# SHT31_2.net
KiCad netlist of a schematic drawn in EAGLE
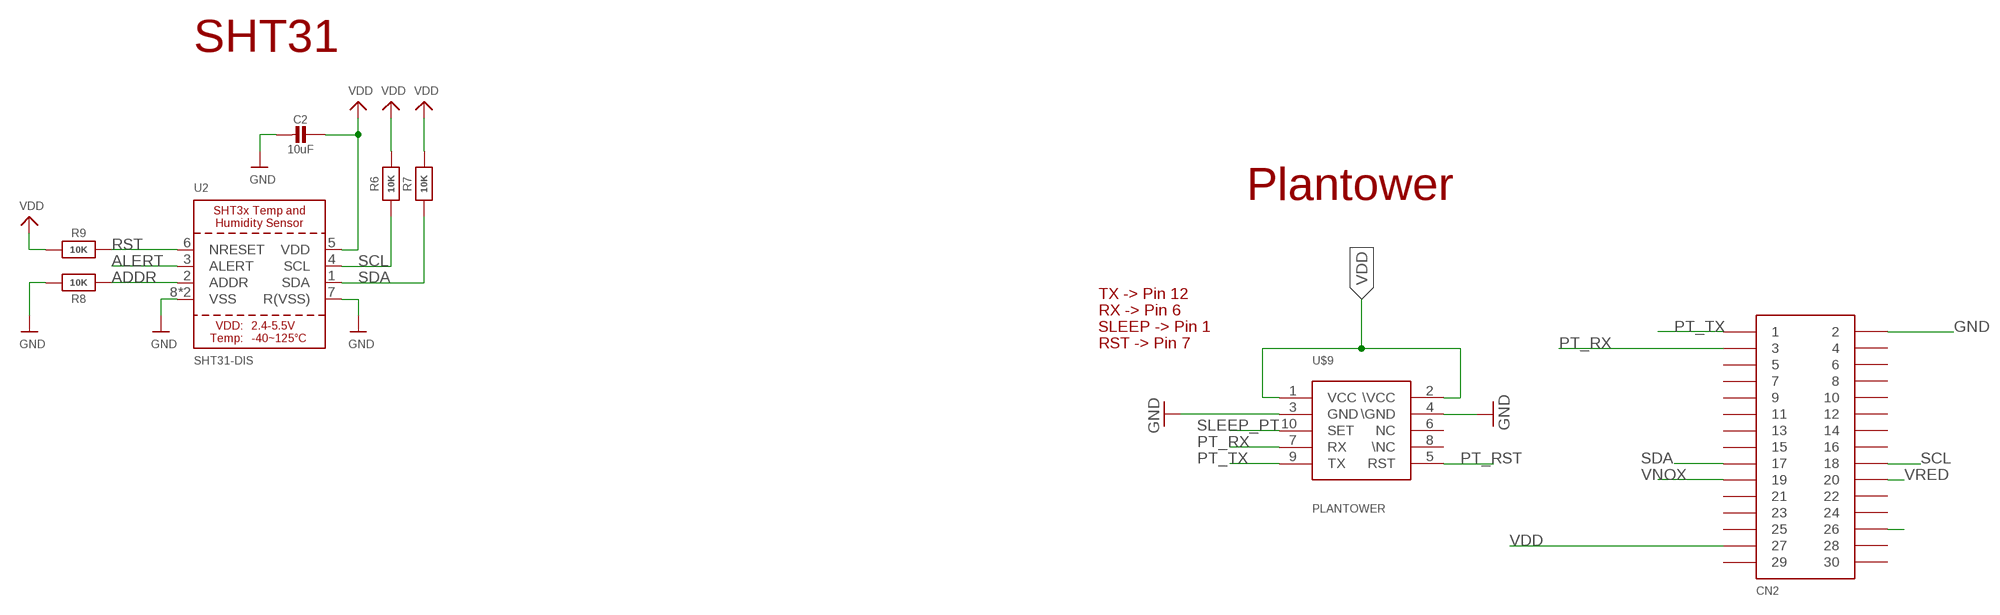
[diagram p0: schematic, sheet 1]
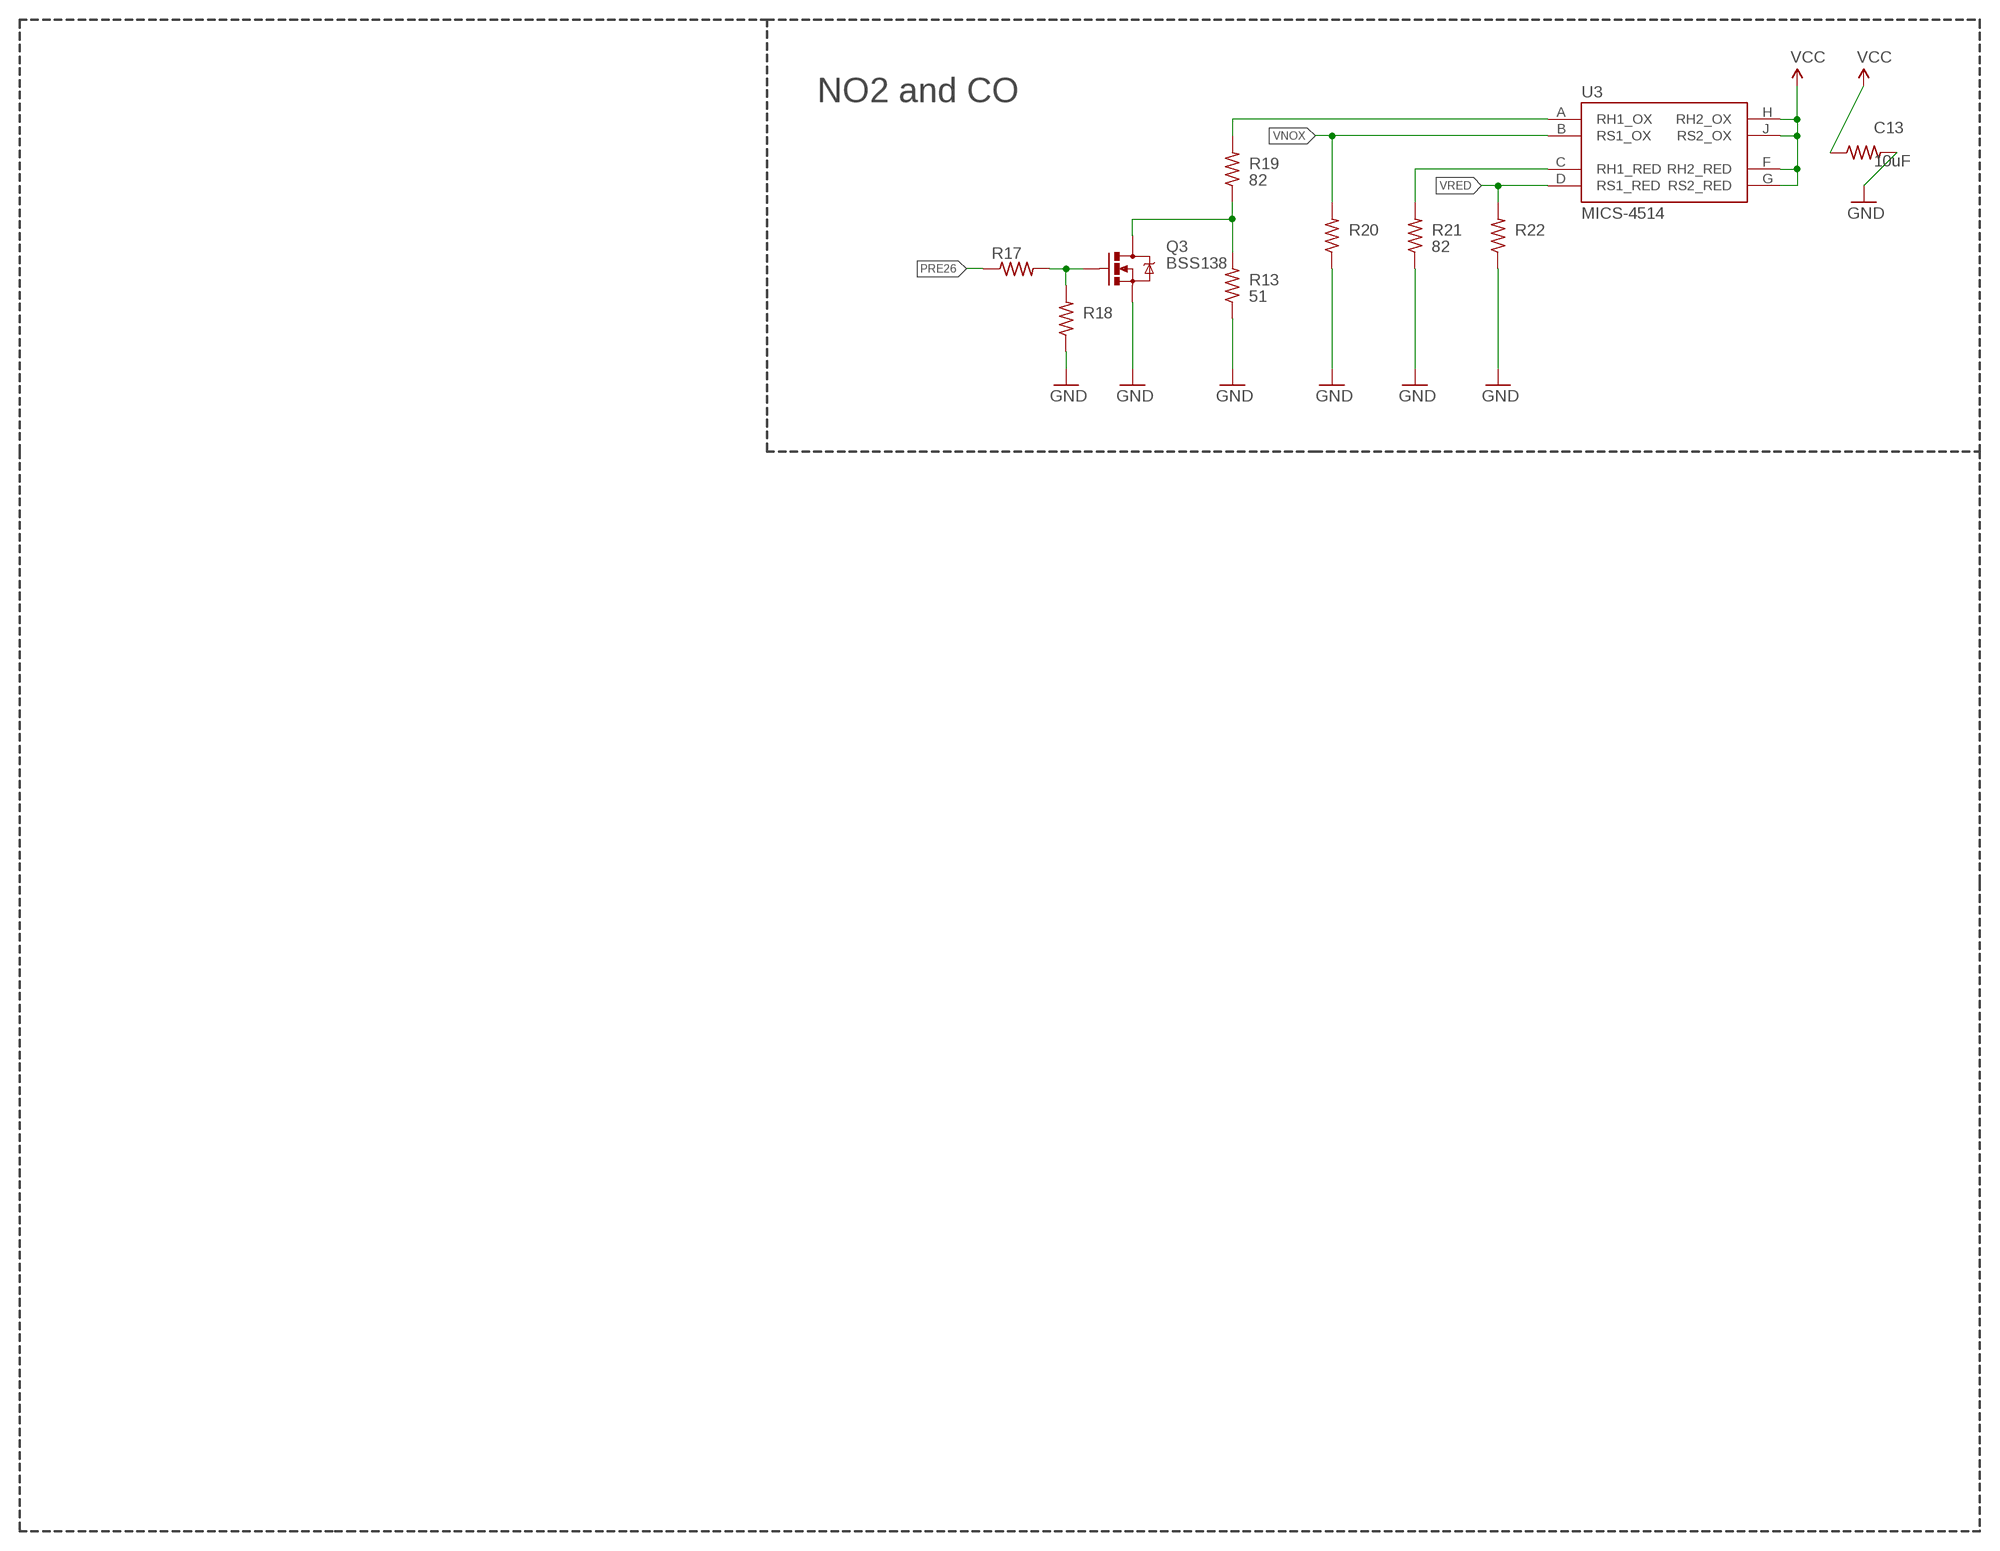
[diagram p1: schematic, sheet 2]

(export (version "E")
  (design (tool "Eeschema 10.0.6"))
  (components
    (comp (ref "C13")
      (value "10uF")
      (footprint "eagle-import:R1206FAB")
      (libsource (lib "eagle-import") (part "RES-US1206FAB"))
    )
    (comp (ref "Q3")
      (value "MOSFET-NCHANNELBSS138")
      (footprint "eagle-import:SOT23-3")
      (fields (field (name "P_NAME") "BSS138"))
      (libsource (lib "eagle-import") (part "MOSFET-NCHANNELBSS138"))
    )
    (comp (ref "R13")
      (value "51")
      (footprint "eagle-import:R1206FAB")
      (libsource (lib "eagle-import") (part "RES-US1206FAB"))
    )
    (comp (ref "R17")
      (value "100")
      (footprint "eagle-import:R1206FAB")
      (libsource (lib "eagle-import") (part "RES-US1206FAB"))
    )
    (comp (ref "R18")
      (value "100K")
      (footprint "eagle-import:R1206FAB")
      (libsource (lib "eagle-import") (part "RES-US1206FAB"))
    )
    (comp (ref "R19")
      (value "82")
      (footprint "eagle-import:R1206FAB")
      (libsource (lib "eagle-import") (part "RES-US1206FAB"))
    )
    (comp (ref "R20")
      (value "22K")
      (footprint "eagle-import:R1206FAB")
      (libsource (lib "eagle-import") (part "RES-US1206FAB"))
    )
    (comp (ref "R21")
      (value "82")
      (footprint "eagle-import:R1206FAB")
      (libsource (lib "eagle-import") (part "RES-US1206FAB"))
    )
    (comp (ref "R22")
      (value "47K")
      (footprint "eagle-import:R1206FAB")
      (libsource (lib "eagle-import") (part "RES-US1206FAB"))
    )
    (comp (ref "U3")
      (value "MICS-4514")
      (footprint "eagle-import:MICS_10-SMD")
      (libsource (lib "eagle-import") (part "MICS-4514"))
    )
    (comp (ref "C2")
      (value "10uF")
      (footprint "eagle-import:_1206")
      (libsource (lib "eagle-import") (part "CAP_CERAMIC_1206"))
    )
    (comp (ref "CN2")
      (value "CON_PINHD-2X15")
      (footprint "eagle-import:2X15SMD")
      (libsource (lib "eagle-import") (part "CON_PINHD-2X15"))
    )
    (comp (ref "R6")
      (value "10K")
      (footprint "eagle-import:_1206MP")
      (libsource (lib "eagle-import") (part "RESISTOR_1206MP"))
    )
    (comp (ref "R7")
      (value "10K")
      (footprint "eagle-import:_1206MP")
      (libsource (lib "eagle-import") (part "RESISTOR_1206MP"))
    )
    (comp (ref "R8")
      (value "10K")
      (footprint "eagle-import:_1206MP")
      (libsource (lib "eagle-import") (part "RESISTOR_1206MP"))
    )
    (comp (ref "R9")
      (value "10K")
      (footprint "eagle-import:_1206MP")
      (libsource (lib "eagle-import") (part "RESISTOR_1206MP"))
    )
    (comp (ref "U$9")
      (value "PLANTOWER")
      (footprint "eagle-import:CONN")
      (libsource (lib "eagle-import") (part "PLANTOWER"))
    )
    (comp (ref "U2")
      (value "SHT31-DIS")
      (footprint "eagle-import:SHT3X")
      (libsource (lib "eagle-import") (part "SHT3X"))
    )
  )
  (nets
    (net (code "1") (name "ADDR") (class "Default")
      (node (ref "R8") (pin "1") (pinfunction "1_1") (pintype "passive"))
      (node (ref "U2") (pin "2") (pinfunction "ADDR_2") (pintype "bidirectional"))
    )
    (net (code "2") (name "ALERT") (class "Default")
      (node (ref "U2") (pin "3") (pinfunction "ALERT_3") (pintype "bidirectional"))
    )
    (net (code "3") (name "GND") (class "Default")
      (node (ref "C13") (pin "2") (pinfunction "2_2") (pintype "passive"))
      (node (ref "C2") (pin "2") (pinfunction "2_2") (pintype "passive"))
      (node (ref "CN2") (pin "P$2") (pinfunction "2_P$2") (pintype "bidirectional"))
      (node (ref "Q3") (pin "2") (pinfunction "S_2") (pintype "passive"))
      (node (ref "R13") (pin "1") (pinfunction "1_1") (pintype "passive"))
      (node (ref "R18") (pin "1") (pinfunction "1_1") (pintype "passive"))
      (node (ref "R20") (pin "1") (pinfunction "1_1") (pintype "passive"))
      (node (ref "R21") (pin "1") (pinfunction "1_1") (pintype "passive"))
      (node (ref "R22") (pin "1") (pinfunction "1_1") (pintype "passive"))
      (node (ref "R8") (pin "2") (pinfunction "2_2") (pintype "passive"))
      (node (ref "U$9") (pin "3") (pinfunction "GND_3") (pintype "bidirectional"))
      (node (ref "U$9") (pin "4") (pinfunction "\\GND_4") (pintype "bidirectional"))
      (node (ref "U2") (pin "7") (pinfunction "R(VSS)_7") (pintype "bidirectional"))
      (node (ref "U2") (pin "8") (pinfunction "VSS_8") (pintype "power_in"))
      (node (ref "U2") (pin "THERMAL") (pinfunction "VSS_THERMAL") (pintype "power_in"))
    )
    (net (code "4") (name "Net-(Q3-D)") (class "Default")
      (node (ref "Q3") (pin "3") (pinfunction "D_3") (pintype "passive"))
      (node (ref "R13") (pin "2") (pinfunction "2_2") (pintype "passive"))
      (node (ref "R19") (pin "1") (pinfunction "1_1") (pintype "passive"))
    )
    (net (code "5") (name "Net-(Q3-G)") (class "Default")
      (node (ref "Q3") (pin "1") (pinfunction "G_1") (pintype "passive"))
      (node (ref "R17") (pin "2") (pinfunction "2_2") (pintype "passive"))
      (node (ref "R18") (pin "2") (pinfunction "2_2") (pintype "passive"))
    )
    (net (code "6") (name "Net-(U3-RH1_OX)") (class "Default")
      (node (ref "R19") (pin "2") (pinfunction "2_2") (pintype "passive"))
      (node (ref "U3") (pin "A") (pinfunction "RH1_OX_A") (pintype "bidirectional"))
    )
    (net (code "7") (name "Net-(U3-RH1_RED)") (class "Default")
      (node (ref "R21") (pin "2") (pinfunction "2_2") (pintype "passive"))
      (node (ref "U3") (pin "C") (pinfunction "RH1_RED_C") (pintype "bidirectional"))
    )
    (net (code "8") (name "PRE26") (class "Default")
      (node (ref "CN2") (pin "P$26") (pinfunction "26_P$26") (pintype "bidirectional"))
      (node (ref "R17") (pin "1") (pinfunction "1_1") (pintype "passive"))
    )
    (net (code "9") (name "PT_RST") (class "Default")
      (node (ref "U$9") (pin "5") (pinfunction "RST_5") (pintype "bidirectional"))
    )
    (net (code "10") (name "PT_RX") (class "Default")
      (node (ref "CN2") (pin "P$3") (pinfunction "3_P$3") (pintype "bidirectional"))
      (node (ref "U$9") (pin "7") (pinfunction "RX_7") (pintype "bidirectional"))
    )
    (net (code "11") (name "PT_TX") (class "Default")
      (node (ref "CN2") (pin "P$1") (pinfunction "1_P$1") (pintype "bidirectional"))
      (node (ref "U$9") (pin "9") (pinfunction "TX_9") (pintype "bidirectional"))
    )
    (net (code "12") (name "RST") (class "Default")
      (node (ref "R9") (pin "2") (pinfunction "2_2") (pintype "passive"))
      (node (ref "U2") (pin "6") (pinfunction "NRESET_6") (pintype "bidirectional"))
    )
    (net (code "13") (name "SCL") (class "Default")
      (node (ref "CN2") (pin "P$18") (pinfunction "18_P$18") (pintype "bidirectional"))
      (node (ref "R6") (pin "1") (pinfunction "1_1") (pintype "passive"))
      (node (ref "U2") (pin "4") (pinfunction "SCL_4") (pintype "bidirectional"))
    )
    (net (code "14") (name "SDA") (class "Default")
      (node (ref "CN2") (pin "P$17") (pinfunction "17_P$17") (pintype "bidirectional"))
      (node (ref "R7") (pin "1") (pinfunction "1_1") (pintype "passive"))
      (node (ref "U2") (pin "1") (pinfunction "SDA_1") (pintype "bidirectional"))
    )
    (net (code "15") (name "SLEEP_PT") (class "Default")
      (node (ref "U$9") (pin "10") (pinfunction "SET_10") (pintype "bidirectional"))
    )
    (net (code "16") (name "VDD") (class "Default")
      (node (ref "C13") (pin "1") (pinfunction "1_1") (pintype "passive"))
      (node (ref "C2") (pin "1") (pinfunction "1_1") (pintype "passive"))
      (node (ref "CN2") (pin "P$27") (pinfunction "27_P$27") (pintype "bidirectional"))
      (node (ref "R6") (pin "2") (pinfunction "2_2") (pintype "passive"))
      (node (ref "R7") (pin "2") (pinfunction "2_2") (pintype "passive"))
      (node (ref "R9") (pin "1") (pinfunction "1_1") (pintype "passive"))
      (node (ref "U$9") (pin "1") (pinfunction "VCC_1") (pintype "bidirectional"))
      (node (ref "U$9") (pin "2") (pinfunction "\\VCC_2") (pintype "bidirectional"))
      (node (ref "U2") (pin "5") (pinfunction "VDD_5") (pintype "power_in"))
      (node (ref "U3") (pin "F") (pinfunction "RH2_RED_F") (pintype "bidirectional"))
      (node (ref "U3") (pin "G") (pinfunction "RS2_RED_G") (pintype "bidirectional"))
      (node (ref "U3") (pin "H") (pinfunction "RH2_OX_H") (pintype "bidirectional"))
      (node (ref "U3") (pin "J") (pinfunction "RS2_OX_J") (pintype "bidirectional"))
    )
    (net (code "17") (name "VNOX") (class "Default")
      (node (ref "CN2") (pin "P$19") (pinfunction "19_P$19") (pintype "bidirectional"))
      (node (ref "R20") (pin "2") (pinfunction "2_2") (pintype "passive"))
      (node (ref "U3") (pin "B") (pinfunction "RS1_OX_B") (pintype "bidirectional"))
    )
    (net (code "18") (name "VRED") (class "Default")
      (node (ref "CN2") (pin "P$20") (pinfunction "20_P$20") (pintype "bidirectional"))
      (node (ref "R22") (pin "2") (pinfunction "2_2") (pintype "passive"))
      (node (ref "U3") (pin "D") (pinfunction "RS1_RED_D") (pintype "bidirectional"))
    )
    (net (code "19") (name "unconnected-(CN2-4-PadP$4)") (class "Default")
      (node (ref "CN2") (pin "P$4") (pinfunction "4_P$4") (pintype "bidirectional"))
    )
    (net (code "20") (name "unconnected-(CN2-5-PadP$5)") (class "Default")
      (node (ref "CN2") (pin "P$5") (pinfunction "5_P$5") (pintype "bidirectional"))
    )
    (net (code "21") (name "unconnected-(CN2-6-PadP$6)") (class "Default")
      (node (ref "CN2") (pin "P$6") (pinfunction "6_P$6") (pintype "bidirectional"))
    )
    (net (code "22") (name "unconnected-(CN2-7-PadP$7)") (class "Default")
      (node (ref "CN2") (pin "P$7") (pinfunction "7_P$7") (pintype "bidirectional"))
    )
    (net (code "23") (name "unconnected-(CN2-8-PadP$8)") (class "Default")
      (node (ref "CN2") (pin "P$8") (pinfunction "8_P$8") (pintype "bidirectional"))
    )
    (net (code "24") (name "unconnected-(CN2-9-PadP$9)") (class "Default")
      (node (ref "CN2") (pin "P$9") (pinfunction "9_P$9") (pintype "bidirectional"))
    )
    (net (code "25") (name "unconnected-(CN2-10-PadP$10)") (class "Default")
      (node (ref "CN2") (pin "P$10") (pinfunction "10_P$10") (pintype "bidirectional"))
    )
    (net (code "26") (name "unconnected-(CN2-11-PadP$11)") (class "Default")
      (node (ref "CN2") (pin "P$11") (pinfunction "11_P$11") (pintype "bidirectional"))
    )
    (net (code "27") (name "unconnected-(CN2-12-PadP$12)") (class "Default")
      (node (ref "CN2") (pin "P$12") (pinfunction "12_P$12") (pintype "bidirectional"))
    )
    (net (code "28") (name "unconnected-(CN2-13-PadP$13)") (class "Default")
      (node (ref "CN2") (pin "P$13") (pinfunction "13_P$13") (pintype "bidirectional"))
    )
    (net (code "29") (name "unconnected-(CN2-14-PadP$14)") (class "Default")
      (node (ref "CN2") (pin "P$14") (pinfunction "14_P$14") (pintype "bidirectional"))
    )
    (net (code "30") (name "unconnected-(CN2-15-PadP$15)") (class "Default")
      (node (ref "CN2") (pin "P$15") (pinfunction "15_P$15") (pintype "bidirectional"))
    )
    (net (code "31") (name "unconnected-(CN2-16-PadP$16)") (class "Default")
      (node (ref "CN2") (pin "P$16") (pinfunction "16_P$16") (pintype "bidirectional"))
    )
    (net (code "32") (name "unconnected-(CN2-21-PadP$21)") (class "Default")
      (node (ref "CN2") (pin "P$21") (pinfunction "21_P$21") (pintype "bidirectional"))
    )
    (net (code "33") (name "unconnected-(CN2-22-PadP$22)") (class "Default")
      (node (ref "CN2") (pin "P$22") (pinfunction "22_P$22") (pintype "bidirectional"))
    )
    (net (code "34") (name "unconnected-(CN2-23-PadP$23)") (class "Default")
      (node (ref "CN2") (pin "P$23") (pinfunction "23_P$23") (pintype "bidirectional"))
    )
    (net (code "35") (name "unconnected-(CN2-24-PadP$24)") (class "Default")
      (node (ref "CN2") (pin "P$24") (pinfunction "24_P$24") (pintype "bidirectional"))
    )
    (net (code "36") (name "unconnected-(CN2-25-PadP$25)") (class "Default")
      (node (ref "CN2") (pin "P$25") (pinfunction "25_P$25") (pintype "bidirectional"))
    )
    (net (code "37") (name "unconnected-(CN2-28-PadP$28)") (class "Default")
      (node (ref "CN2") (pin "P$28") (pinfunction "28_P$28") (pintype "bidirectional"))
    )
    (net (code "38") (name "unconnected-(CN2-29-PadP$29)") (class "Default")
      (node (ref "CN2") (pin "P$29") (pinfunction "29_P$29") (pintype "bidirectional"))
    )
    (net (code "39") (name "unconnected-(CN2-30-PadP$30)") (class "Default")
      (node (ref "CN2") (pin "P$30") (pinfunction "30_P$30") (pintype "bidirectional"))
    )
    (net (code "40") (name "unconnected-(U$9-NC-Pad6)") (class "Default")
      (node (ref "U$9") (pin "6") (pinfunction "NC_6") (pintype "bidirectional"))
    )
    (net (code "41") (name "unconnected-(U$9-\\NC-Pad8)") (class "Default")
      (node (ref "U$9") (pin "8") (pinfunction "\\NC_8") (pintype "bidirectional"))
    )
  )
)
